# Aux_Inputs.net
KiCad netlist of a schematic drawn in Altium Designer
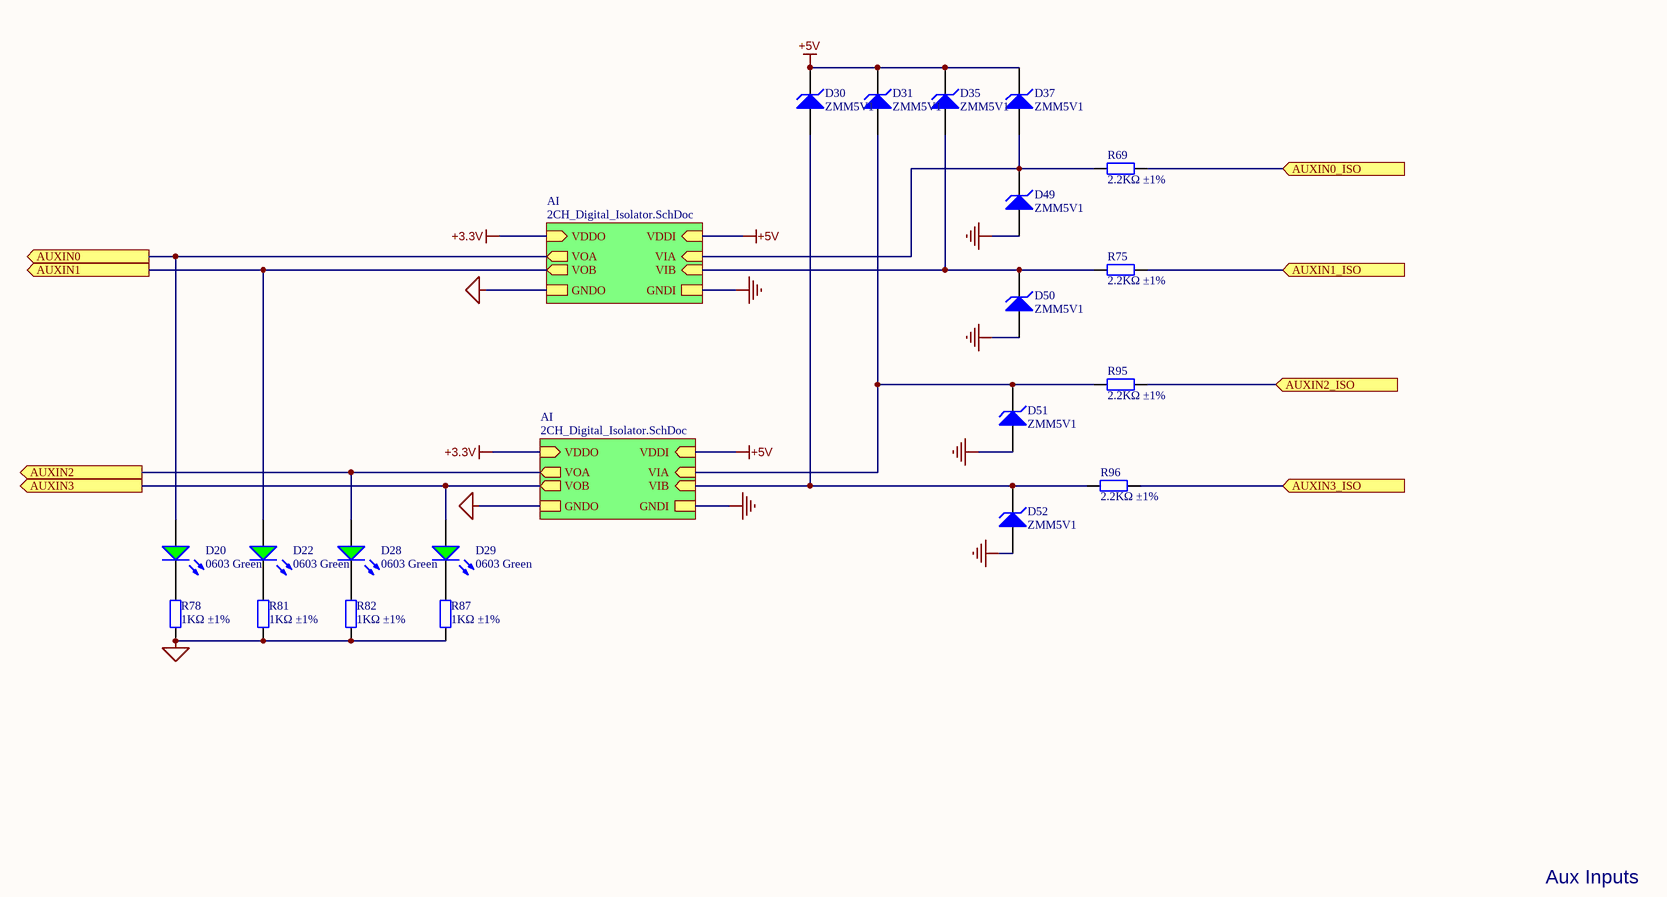
[diagram p0: Aux_Inputs.SchDoc]

(export (version "E")
  (design (tool "Eeschema 10.0.6"))
  (components
    (comp (ref "D20")
      (value "0603 Green")
      (footprint "0603_LED_S1")
      (description "LED")
      (libsource (lib "LED") (part "0603 LED Green"))
    )
    (comp (ref "D22")
      (value "0603 Green")
      (footprint "0603_LED_S1")
      (description "LED")
      (libsource (lib "LED") (part "0603 LED Green"))
    )
    (comp (ref "D28")
      (value "0603 Green")
      (footprint "0603_LED_S1")
      (description "LED")
      (libsource (lib "LED") (part "0603 LED Green"))
    )
    (comp (ref "D29")
      (value "0603 Green")
      (footprint "0603_LED_S1")
      (description "LED")
      (libsource (lib "LED") (part "0603 LED Green"))
    )
    (comp (ref "D30")
      (value "ZMM5V1")
      (footprint "LL-34")
      (description "500mW - 0.1uA @ 1V 5.1V LL-34 Zener Diodes ROHS")
      (libsource (lib "Zener") (part "LL-34 ZMM5V6"))
    )
    (comp (ref "D31")
      (value "ZMM5V1")
      (footprint "LL-34")
      (description "500mW - 0.1uA @ 1V 5.1V LL-34 Zener Diodes ROHS")
      (libsource (lib "Zener") (part "LL-34 ZMM5V6"))
    )
    (comp (ref "D35")
      (value "ZMM5V1")
      (footprint "LL-34")
      (description "500mW - 0.1uA @ 1V 5.1V LL-34 Zener Diodes ROHS")
      (libsource (lib "Zener") (part "LL-34 ZMM5V6"))
    )
    (comp (ref "D37")
      (value "ZMM5V1")
      (footprint "LL-34")
      (description "500mW - 0.1uA @ 1V 5.1V LL-34 Zener Diodes ROHS")
      (libsource (lib "Zener") (part "LL-34 ZMM5V6"))
    )
    (comp (ref "D49")
      (value "ZMM5V1")
      (footprint "LL-34")
      (description "500mW - 0.1uA @ 1V 5.1V LL-34 Zener Diodes ROHS")
      (libsource (lib "Zener") (part "LL-34 ZMM5V6"))
    )
    (comp (ref "D50")
      (value "ZMM5V1")
      (footprint "LL-34")
      (description "500mW - 0.1uA @ 1V 5.1V LL-34 Zener Diodes ROHS")
      (libsource (lib "Zener") (part "LL-34 ZMM5V6"))
    )
    (comp (ref "D51")
      (value "ZMM5V1")
      (footprint "LL-34")
      (description "500mW - 0.1uA @ 1V 5.1V LL-34 Zener Diodes ROHS")
      (libsource (lib "Zener") (part "LL-34 ZMM5V6"))
    )
    (comp (ref "D52")
      (value "ZMM5V1")
      (footprint "LL-34")
      (description "500mW - 0.1uA @ 1V 5.1V LL-34 Zener Diodes ROHS")
      (libsource (lib "Zener") (part "LL-34 ZMM5V6"))
    )
    (comp (ref "R69")
      (value "2.2KΩ ±1%")
      (footprint "0603_R")
      (description "Chip resistor")
      (fields (field (name "MANUFACTURER") "Uniroyal Elec") (field (name "PARTNUMBER") "0603WAF2201T5E"))
      (libsource (lib "RES") (part "0603 2.2K (2201) 1%"))
    )
    (comp (ref "R75")
      (value "2.2KΩ ±1%")
      (footprint "0603_R")
      (description "Chip resistor")
      (fields (field (name "MANUFACTURER") "Uniroyal Elec") (field (name "PARTNUMBER") "0603WAF2201T5E"))
      (libsource (lib "RES") (part "0603 2.2K (2201) 1%"))
    )
    (comp (ref "R78")
      (value "1KΩ ±1%")
      (footprint "0603_R")
      (description "Chip resistor")
      (fields (field (name "MANUFACTURER") "Uniroyal Elec") (field (name "PARTNUMBER") "0603WAF1001T5E"))
      (libsource (lib "RES") (part "0603 1K (1001) 1%"))
    )
    (comp (ref "R81")
      (value "1KΩ ±1%")
      (footprint "0603_R")
      (description "Chip resistor")
      (fields (field (name "MANUFACTURER") "Uniroyal Elec") (field (name "PARTNUMBER") "0603WAF1001T5E"))
      (libsource (lib "RES") (part "0603 1K (1001) 1%"))
    )
    (comp (ref "R82")
      (value "1KΩ ±1%")
      (footprint "0603_R")
      (description "Chip resistor")
      (fields (field (name "MANUFACTURER") "Uniroyal Elec") (field (name "PARTNUMBER") "0603WAF1001T5E"))
      (libsource (lib "RES") (part "0603 1K (1001) 1%"))
    )
    (comp (ref "R87")
      (value "1KΩ ±1%")
      (footprint "0603_R")
      (description "Chip resistor")
      (fields (field (name "MANUFACTURER") "Uniroyal Elec") (field (name "PARTNUMBER") "0603WAF1001T5E"))
      (libsource (lib "RES") (part "0603 1K (1001) 1%"))
    )
    (comp (ref "R95")
      (value "2.2KΩ ±1%")
      (footprint "0603_R")
      (description "Chip resistor")
      (fields (field (name "MANUFACTURER") "Uniroyal Elec") (field (name "PARTNUMBER") "0603WAF2201T5E"))
      (libsource (lib "RES") (part "0603 2.2K (2201) 1%"))
    )
    (comp (ref "R96")
      (value "2.2KΩ ±1%")
      (footprint "0603_R")
      (description "Chip resistor")
      (fields (field (name "MANUFACTURER") "Uniroyal Elec") (field (name "PARTNUMBER") "0603WAF2201T5E"))
      (libsource (lib "RES") (part "0603 2.2K (2201) 1%"))
    )
  )
  (nets
    (net (code "2") (name "+5V") (class "Default")
      (node (ref "D30") (pin "2") (pinfunction "K_2") (pintype "passive"))
      (node (ref "D31") (pin "2") (pinfunction "K_2") (pintype "passive"))
      (node (ref "D35") (pin "2") (pinfunction "K_2") (pintype "passive"))
      (node (ref "D37") (pin "2") (pinfunction "K_2") (pintype "passive"))
    )
    (net (code "3") (name "/AUXIN0") (class "Default")
      (node (ref "D20") (pin "A") (pinfunction "A_A") (pintype "passive"))
    )
    (net (code "4") (name "/AUXIN0_ISO") (class "Default")
      (node (ref "R69") (pin "1") (pinfunction "1_1") (pintype "passive"))
    )
    (net (code "5") (name "/AUXIN1") (class "Default")
      (node (ref "D22") (pin "A") (pinfunction "A_A") (pintype "passive"))
    )
    (net (code "6") (name "/AUXIN1_ISO") (class "Default")
      (node (ref "R75") (pin "1") (pinfunction "1_1") (pintype "passive"))
    )
    (net (code "7") (name "/AUXIN2") (class "Default")
      (node (ref "D28") (pin "A") (pinfunction "A_A") (pintype "passive"))
    )
    (net (code "8") (name "/AUXIN2_ISO") (class "Default")
      (node (ref "R95") (pin "1") (pinfunction "1_1") (pintype "passive"))
    )
    (net (code "9") (name "/AUXIN3") (class "Default")
      (node (ref "D29") (pin "A") (pinfunction "A_A") (pintype "passive"))
    )
    (net (code "10") (name "/AUXIN3_ISO") (class "Default")
      (node (ref "R96") (pin "1") (pinfunction "1_1") (pintype "passive"))
    )
    (net (code "11") (name "/VIA") (class "Default")
      (node (ref "D37") (pin "1") (pinfunction "A_1") (pintype "passive"))
      (node (ref "D49") (pin "2") (pinfunction "K_2") (pintype "passive"))
      (node (ref "R69") (pin "2") (pinfunction "2_2") (pintype "passive"))
    )
    (net (code "12") (name "/VIA_1") (class "Default")
      (node (ref "D31") (pin "1") (pinfunction "A_1") (pintype "passive"))
      (node (ref "D51") (pin "2") (pinfunction "K_2") (pintype "passive"))
      (node (ref "R95") (pin "2") (pinfunction "2_2") (pintype "passive"))
    )
    (net (code "13") (name "/VIB") (class "Default")
      (node (ref "D30") (pin "1") (pinfunction "A_1") (pintype "passive"))
      (node (ref "D52") (pin "2") (pinfunction "K_2") (pintype "passive"))
      (node (ref "R96") (pin "2") (pinfunction "2_2") (pintype "passive"))
    )
    (net (code "14") (name "/VIB_1") (class "Default")
      (node (ref "D35") (pin "1") (pinfunction "A_1") (pintype "passive"))
      (node (ref "D50") (pin "2") (pinfunction "K_2") (pintype "passive"))
      (node (ref "R75") (pin "2") (pinfunction "2_2") (pintype "passive"))
    )
    (net (code "15") (name "GND") (class "Default")
      (node (ref "D49") (pin "1") (pinfunction "A_1") (pintype "passive"))
      (node (ref "D50") (pin "1") (pinfunction "A_1") (pintype "passive"))
      (node (ref "D51") (pin "1") (pinfunction "A_1") (pintype "passive"))
      (node (ref "D52") (pin "1") (pinfunction "A_1") (pintype "passive"))
    )
    (net (code "16") (name "MCU_GND") (class "Default")
      (node (ref "R78") (pin "2") (pinfunction "2_2") (pintype "passive"))
      (node (ref "R81") (pin "2") (pinfunction "2_2") (pintype "passive"))
      (node (ref "R82") (pin "2") (pinfunction "2_2") (pintype "passive"))
      (node (ref "R87") (pin "2") (pinfunction "2_2") (pintype "passive"))
    )
    (net (code "17") (name "Net-(D20-PadK)") (class "Default")
      (node (ref "D20") (pin "K") (pinfunction "K_K") (pintype "passive"))
      (node (ref "R78") (pin "1") (pinfunction "1_1") (pintype "passive"))
    )
    (net (code "18") (name "Net-(D22-PadK)") (class "Default")
      (node (ref "D22") (pin "K") (pinfunction "K_K") (pintype "passive"))
      (node (ref "R81") (pin "1") (pinfunction "1_1") (pintype "passive"))
    )
    (net (code "19") (name "Net-(D28-PadK)") (class "Default")
      (node (ref "D28") (pin "K") (pinfunction "K_K") (pintype "passive"))
      (node (ref "R82") (pin "1") (pinfunction "1_1") (pintype "passive"))
    )
    (net (code "20") (name "Net-(D29-PadK)") (class "Default")
      (node (ref "D29") (pin "K") (pinfunction "K_K") (pintype "passive"))
      (node (ref "R87") (pin "1") (pinfunction "1_1") (pintype "passive"))
    )
  )
)
